# comparator.net
KiCad netlist of a schematic drawn in EAGLE
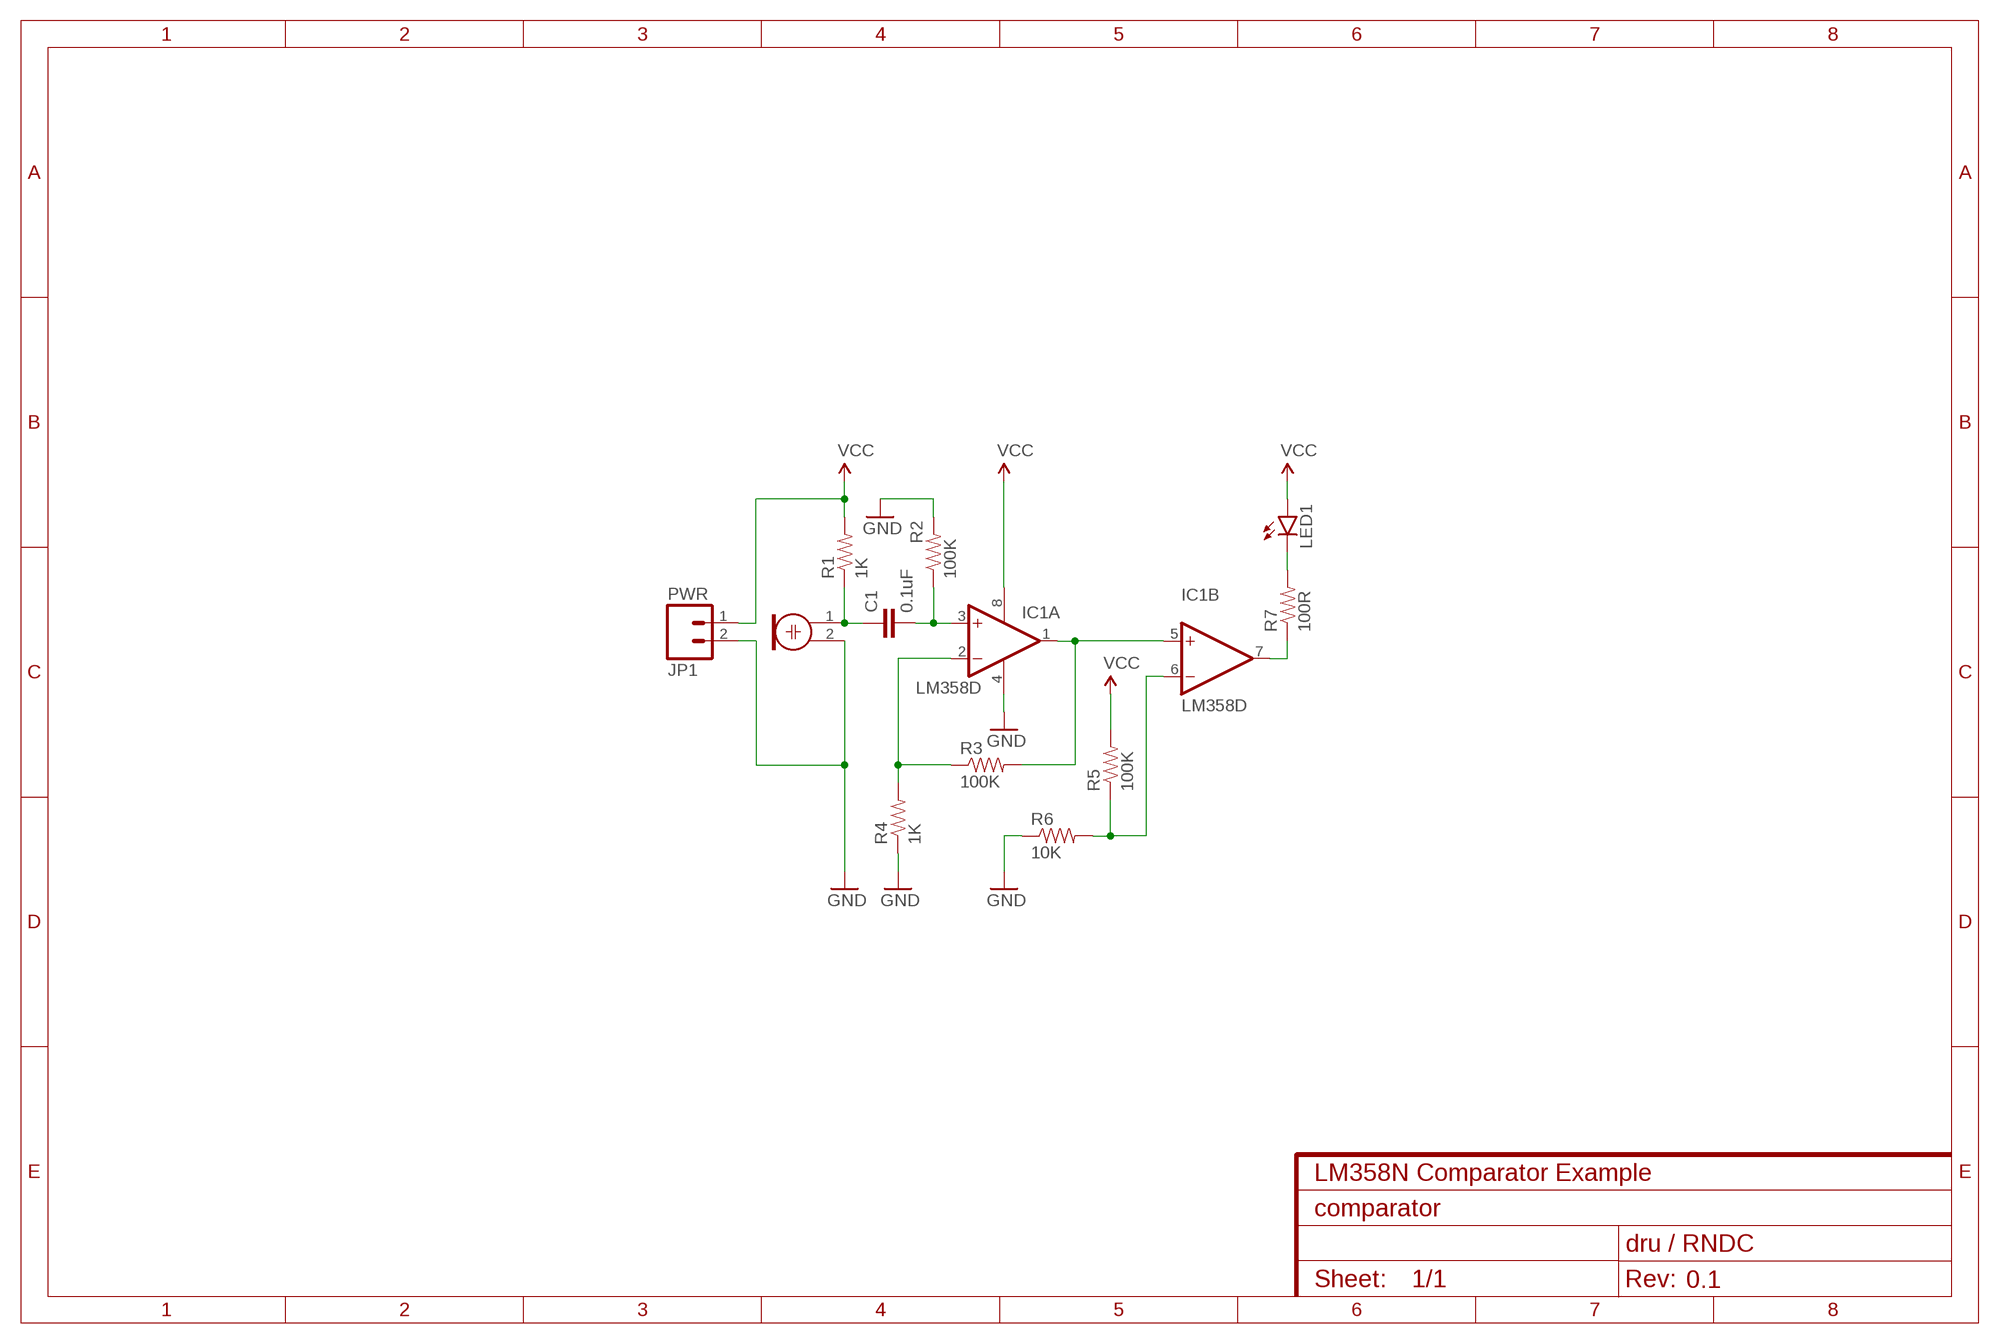
[diagram p0: schematic, sheet 1]

(export (version "E")
  (design (tool "Eeschema 10.0.6"))
  (components
    (comp (ref "C1")
      (value "0.1uF")
      (footprint "eagle-import:0805")
      (libsource (lib "eagle-import") (part "CAP0805"))
    )
    (comp (ref "IC1")
      (value "LM358D")
      (footprint "eagle-import:SO08")
      (libsource (lib "eagle-import") (part "LM358D"))
    )
    (comp (ref "JP1")
      (value "PWR")
      (footprint "eagle-import:1X02")
      (libsource (lib "eagle-import") (part "M02PTH"))
    )
    (comp (ref "LED1")
      (value "LED5MM")
      (footprint "eagle-import:LED5MM")
      (libsource (lib "eagle-import") (part "LED5MM"))
    )
    (comp (ref "MIC")
      (value "ELECTRET_MICROPHON-WM-61A")
      (footprint "eagle-import:WM-61A")
      (libsource (lib "eagle-import") (part "ELECTRET_MICROPHON-WM-61A"))
    )
    (comp (ref "R1")
      (value "1K")
      (footprint "eagle-import:0603-RES")
      (libsource (lib "eagle-import") (part "RESISTOR0603"))
    )
    (comp (ref "R2")
      (value "100K")
      (footprint "eagle-import:0603-RES")
      (libsource (lib "eagle-import") (part "RESISTOR0603"))
    )
    (comp (ref "R3")
      (value "100K")
      (footprint "eagle-import:0603-RES")
      (libsource (lib "eagle-import") (part "RESISTOR0603"))
    )
    (comp (ref "R4")
      (value "1K")
      (footprint "eagle-import:0603-RES")
      (libsource (lib "eagle-import") (part "RESISTOR0603"))
    )
    (comp (ref "R5")
      (value "100K")
      (footprint "eagle-import:0603-RES")
      (libsource (lib "eagle-import") (part "RESISTOR0603"))
    )
    (comp (ref "R6")
      (value "10K")
      (footprint "eagle-import:0603-RES")
      (libsource (lib "eagle-import") (part "RESISTOR0603"))
    )
    (comp (ref "R7")
      (value "100R")
      (footprint "eagle-import:0603-RES")
      (libsource (lib "eagle-import") (part "RESISTOR0603"))
    )
  )
  (nets
    (net (code "1") (name "GND") (class "Default")
      (node (ref "IC1") (pin "4") (pinfunction "V-_4") (pintype "power_in"))
      (node (ref "JP1") (pin "2") (pinfunction "2_2") (pintype "passive"))
      (node (ref "MIC") (pin "2") (pinfunction "2_2") (pintype "passive"))
      (node (ref "R2") (pin "2") (pinfunction "2_2") (pintype "passive"))
      (node (ref "R4") (pin "1") (pinfunction "1_1") (pintype "passive"))
      (node (ref "R6") (pin "1") (pinfunction "1_1") (pintype "passive"))
    )
    (net (code "2") (name "Net-(C1-Pad1)") (class "Default")
      (node (ref "C1") (pin "1") (pinfunction "1_1") (pintype "passive"))
      (node (ref "MIC") (pin "1") (pinfunction "1_1") (pintype "passive"))
      (node (ref "R1") (pin "1") (pinfunction "1_1") (pintype "passive"))
    )
    (net (code "3") (name "Net-(IC1A-+IN)") (class "Default")
      (node (ref "C1") (pin "2") (pinfunction "2_2") (pintype "passive"))
      (node (ref "IC1") (pin "3") (pinfunction "+IN_3") (pintype "input"))
      (node (ref "R2") (pin "1") (pinfunction "1_1") (pintype "passive"))
    )
    (net (code "4") (name "Net-(IC1A--IN)") (class "Default")
      (node (ref "IC1") (pin "2") (pinfunction "-IN_2") (pintype "input"))
      (node (ref "R3") (pin "1") (pinfunction "1_1") (pintype "passive"))
      (node (ref "R4") (pin "2") (pinfunction "2_2") (pintype "passive"))
    )
    (net (code "5") (name "Net-(IC1A-OUT)") (class "Default")
      (node (ref "IC1") (pin "1") (pinfunction "OUT_1") (pintype "output"))
      (node (ref "IC1") (pin "5") (pinfunction "+IN_5") (pintype "input"))
      (node (ref "R3") (pin "2") (pinfunction "2_2") (pintype "passive"))
    )
    (net (code "6") (name "Net-(IC1B--IN)") (class "Default")
      (node (ref "IC1") (pin "6") (pinfunction "-IN_6") (pintype "input"))
      (node (ref "R5") (pin "1") (pinfunction "1_1") (pintype "passive"))
      (node (ref "R6") (pin "2") (pinfunction "2_2") (pintype "passive"))
    )
    (net (code "7") (name "Net-(IC1B-OUT)") (class "Default")
      (node (ref "IC1") (pin "7") (pinfunction "OUT_7") (pintype "output"))
      (node (ref "R7") (pin "1") (pinfunction "1_1") (pintype "passive"))
    )
    (net (code "8") (name "Net-(LED1-C)") (class "Default")
      (node (ref "LED1") (pin "K") (pinfunction "C_K") (pintype "passive"))
      (node (ref "R7") (pin "2") (pinfunction "2_2") (pintype "passive"))
    )
    (net (code "9") (name "VCC") (class "Default")
      (node (ref "IC1") (pin "8") (pinfunction "V+_8") (pintype "power_in"))
      (node (ref "JP1") (pin "1") (pinfunction "1_1") (pintype "passive"))
      (node (ref "LED1") (pin "A") (pinfunction "A_A") (pintype "passive"))
      (node (ref "R1") (pin "2") (pinfunction "2_2") (pintype "passive"))
      (node (ref "R5") (pin "2") (pinfunction "2_2") (pintype "passive"))
    )
  )
)
